# EasyEDA_Pro_project.net
KiCad netlist of a schematic drawn in EasyEDA Pro
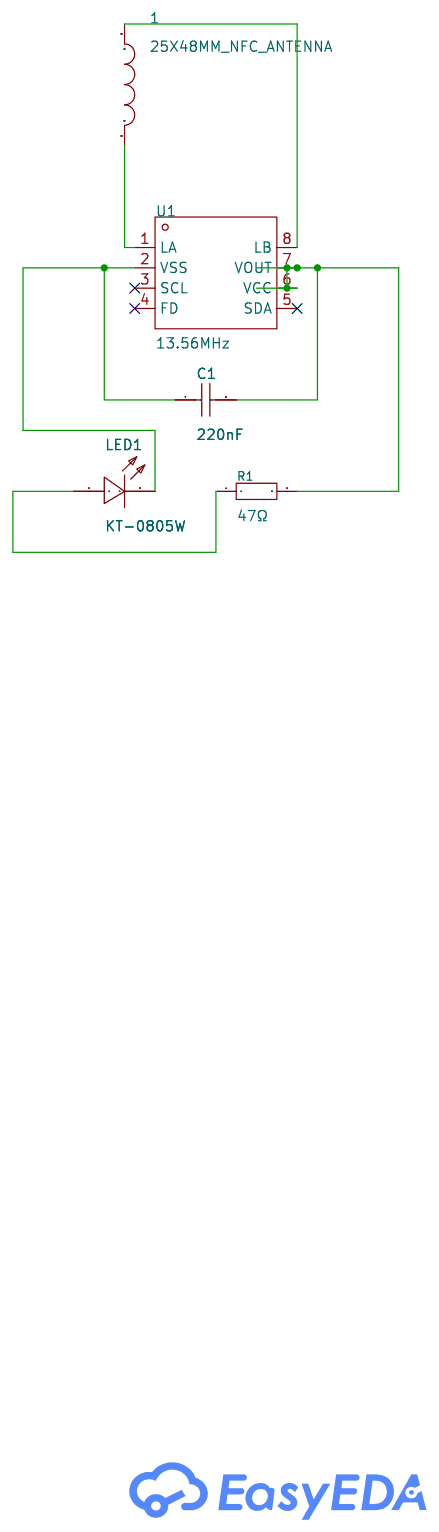
[diagram p0: schematic sheet]

(export (version "E")
  (design (tool "Eeschema 10.0.6"))
  (components
    (comp (ref "1") (value "25X48MM_NFC_ANTENNA") (libsource (lib "easyedapro") (part "25X48MM_NFC_ANTENNA")))
    (comp (ref "C1")
      (value "220nF")
      (footprint "easyedapro:C0603")
      (fields
        (field (name "Manufacturer Part") "CL10B224KA8NNNC")
        (field (name "Manufacturer") "SAMSUNG(三星)")
      )
      (libsource (lib "easyedapro") (part "CL10B224KA8NNNC"))
    )
    (comp (ref "LED1")
      (value "KT-0805W")
      (footprint "easyedapro:LED0805-R-RD")
      (fields (field (name "Manufacturer") "KENTO"))
      (libsource (lib "easyedapro") (part "whiteLEDSMD"))
    )
    (comp (ref "R1")
      (value "47Ω")
      (footprint "easyedapro:R0603")
      (fields
        (field (name "Manufacturer Part") "0603WAF470JT5E")
        (field (name "Manufacturer") "UNI-ROYAL(厚声)")
      )
      (libsource (lib "easyedapro") (part "0603WAF470JT5E"))
    )
    (comp (ref "U1")
      (value "13.56MHz")
      (footprint "easyedapro:XQFN-8_L1.6-W1.6-P0.50-BL_NT3H2111W0FHKH")
      (fields (field (name "Manufacturer Part") "NT3H2111W0FHKH") (field (name "Manufacturer") "NXP(恩智浦)"))
      (libsource (lib "easyedapro") (part "NT3H2111W0FHKH"))
    )
  )
  (nets
    (net (code "1") (name "Net-(LED1-A)") (class "Default")
      (node (ref "LED1") (pin "1") (pinfunction "A_1") (pintype "unspecified"))
      (node (ref "R1") (pin "1") (pinfunction "1_1") (pintype "input"))
    )
    (net (code "2") (name "Net-(LED1-K)") (class "Default")
      (node (ref "C1") (pin "1") (pinfunction "1_1") (pintype "input"))
      (node (ref "LED1") (pin "2") (pinfunction "K_2") (pintype "unspecified"))
      (node (ref "U1") (pin "2") (pinfunction "VSS_2") (pintype "unspecified"))
    )
    (net (code "3") (name "Net-(U1-LA)") (class "Default")
      (node (ref "1") (pin "P$2") (pinfunction "P$2_P$2") (pintype "bidirectional"))
      (node (ref "U1") (pin "1") (pinfunction "LA_1") (pintype "unspecified"))
    )
    (net (code "4") (name "Net-(U1-LB)") (class "Default")
      (node (ref "1") (pin "P$1") (pinfunction "P$1_P$1") (pintype "bidirectional"))
      (node (ref "U1") (pin "8") (pinfunction "LB_8") (pintype "unspecified"))
    )
    (net (code "5") (name "Net-(U1-VCC)") (class "Default")
      (node (ref "C1") (pin "2") (pinfunction "2_2") (pintype "input"))
      (node (ref "R1") (pin "2") (pinfunction "2_2") (pintype "input"))
      (node (ref "U1") (pin "6") (pinfunction "VCC_6") (pintype "unspecified"))
      (node (ref "U1") (pin "7") (pinfunction "VOUT_7") (pintype "unspecified"))
    )
    (net (code "6") (name "unconnected-(U1-FD-Pad4)") (class "Default")
      (node (ref "U1") (pin "4") (pinfunction "FD_4") (pintype "unspecified+no_connect"))
    )
    (net (code "7") (name "unconnected-(U1-SCL-Pad3)") (class "Default")
      (node (ref "U1") (pin "3") (pinfunction "SCL_3") (pintype "unspecified+no_connect"))
    )
    (net (code "8") (name "unconnected-(U1-SDA-Pad5)") (class "Default")
      (node (ref "U1") (pin "5") (pinfunction "SDA_5") (pintype "unspecified+no_connect"))
    )
  )
)
